# V-00780-00.net
KiCad netlist of a schematic drawn in EAGLE
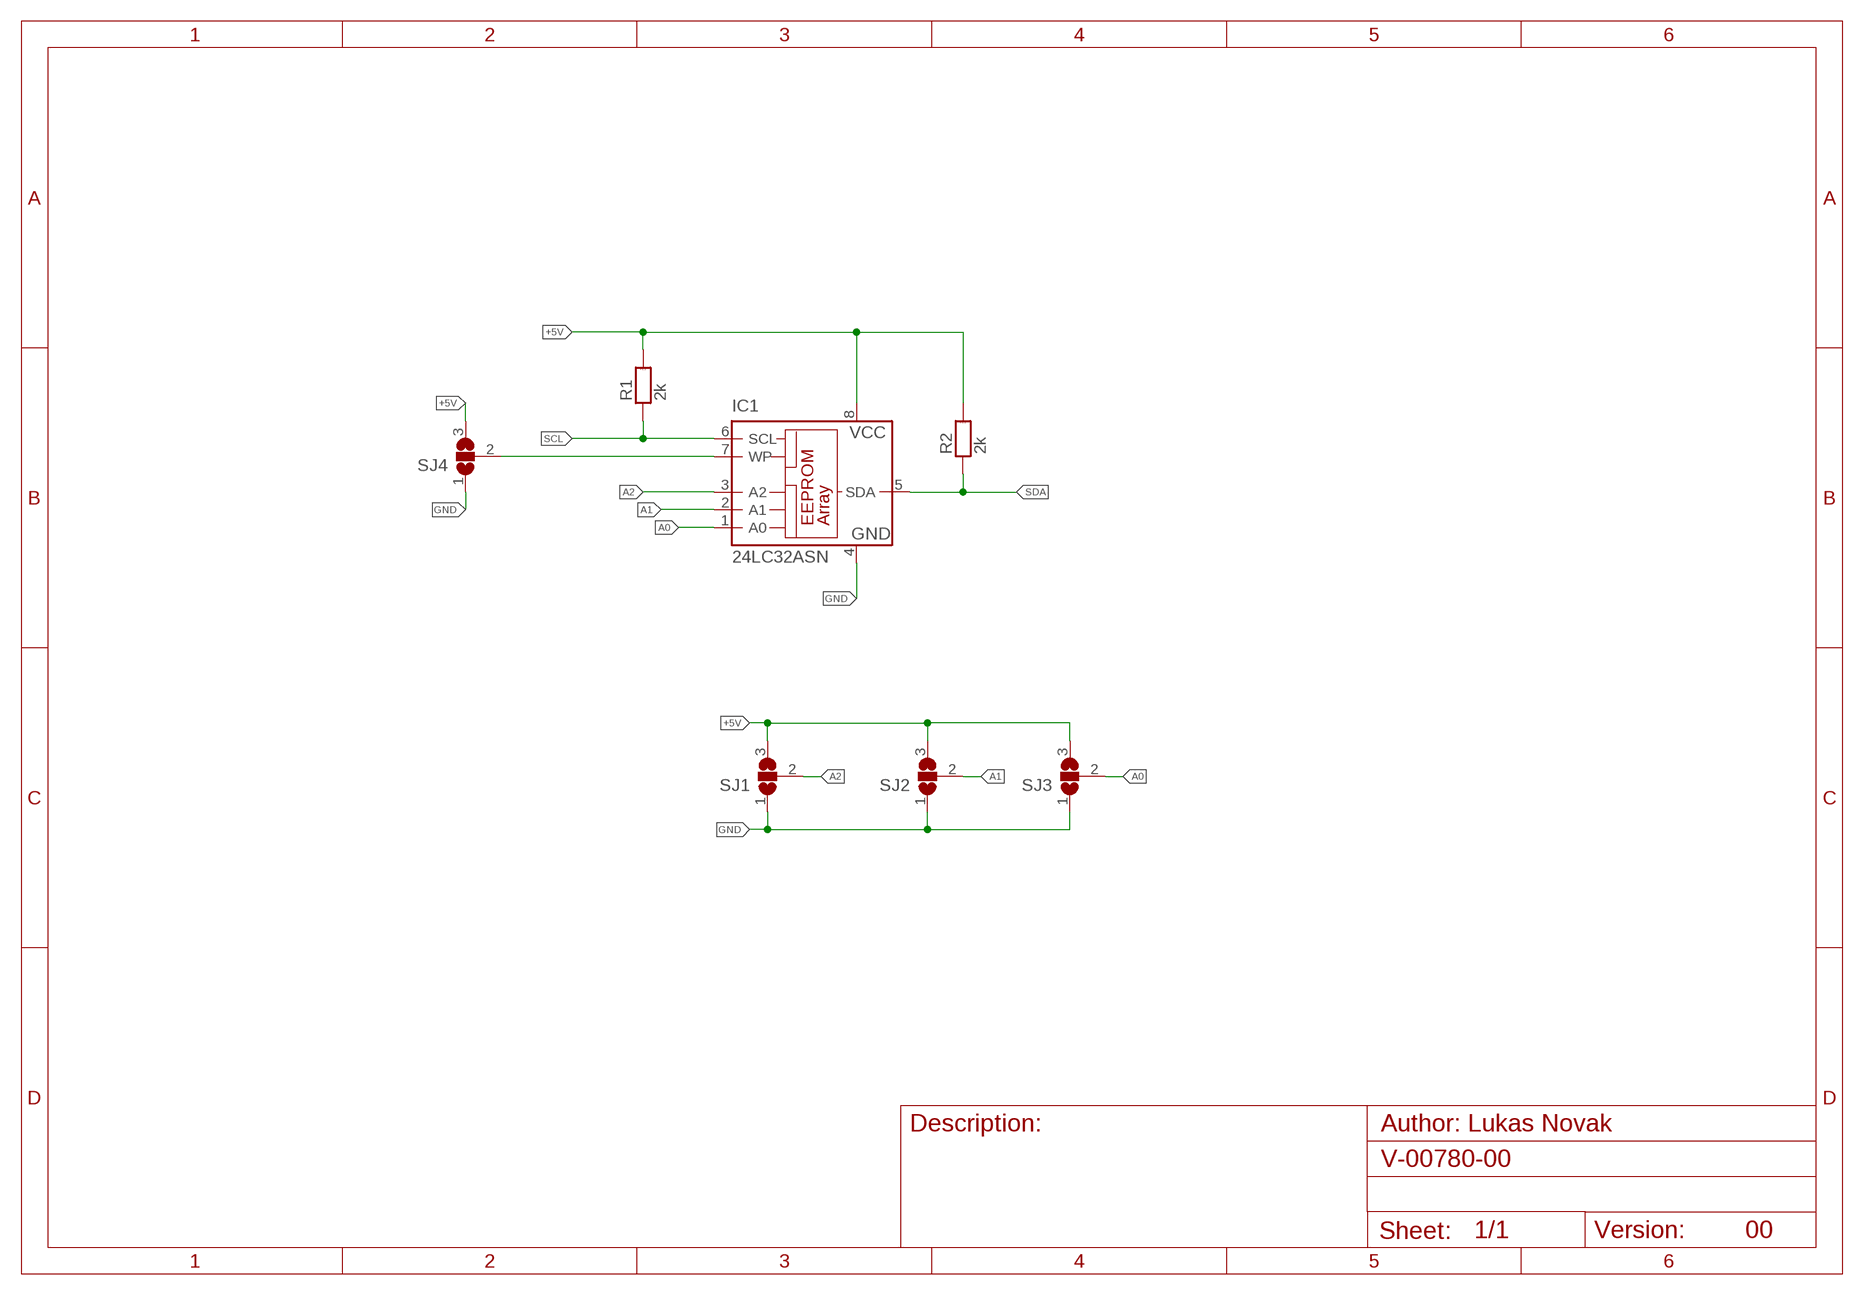
[diagram p0: schematic, sheet 1]

(export (version "E")
  (design (tool "Eeschema 10.0.6"))
  (components
    (comp (ref "IC1")
      (value "24LC32ASN")
      (footprint "eagle-import:SO-08")
      (fields (field (name "MF") "MICROCHIP") (field (name "MPN") "24LC32A/SN"))
      (libsource (lib "eagle-import") (part "24SNLC32A"))
    )
    (comp (ref "R1")
      (value "2k")
      (footprint "eagle-import:1206")
      (libsource (lib "eagle-import") (part "R_1206"))
    )
    (comp (ref "R2")
      (value "2k")
      (footprint "eagle-import:1206")
      (libsource (lib "eagle-import") (part "R_1206"))
    )
    (comp (ref "SJ1")
      (value "SJ2W")
      (footprint "eagle-import:SJ_2")
      (libsource (lib "eagle-import") (part "SJ2W"))
    )
    (comp (ref "SJ2")
      (value "SJ2W")
      (footprint "eagle-import:SJ_2")
      (libsource (lib "eagle-import") (part "SJ2W"))
    )
    (comp (ref "SJ3")
      (value "SJ2W")
      (footprint "eagle-import:SJ_2")
      (libsource (lib "eagle-import") (part "SJ2W"))
    )
    (comp (ref "SJ4")
      (value "SJ2W")
      (footprint "eagle-import:SJ_2")
      (libsource (lib "eagle-import") (part "SJ2W"))
    )
  )
  (nets
    (net (code "1") (name "+5V") (class "Default")
      (node (ref "IC1") (pin "8") (pinfunction "VCC_8") (pintype "power_in"))
      (node (ref "R1") (pin "2") (pinfunction "2_2") (pintype "passive"))
      (node (ref "R2") (pin "2") (pinfunction "2_2") (pintype "passive"))
      (node (ref "SJ1") (pin "3") (pinfunction "3_3") (pintype "passive"))
      (node (ref "SJ2") (pin "3") (pinfunction "3_3") (pintype "passive"))
      (node (ref "SJ3") (pin "3") (pinfunction "3_3") (pintype "passive"))
      (node (ref "SJ4") (pin "3") (pinfunction "3_3") (pintype "passive"))
    )
    (net (code "2") (name "A0") (class "Default")
      (node (ref "IC1") (pin "1") (pinfunction "A0_1") (pintype "input"))
      (node (ref "SJ3") (pin "2") (pinfunction "2_2") (pintype "passive"))
    )
    (net (code "3") (name "A1") (class "Default")
      (node (ref "IC1") (pin "2") (pinfunction "A1_2") (pintype "input"))
      (node (ref "SJ2") (pin "2") (pinfunction "2_2") (pintype "passive"))
    )
    (net (code "4") (name "A2") (class "Default")
      (node (ref "IC1") (pin "3") (pinfunction "A2_3") (pintype "input"))
      (node (ref "SJ1") (pin "2") (pinfunction "2_2") (pintype "passive"))
    )
    (net (code "5") (name "GND") (class "Default")
      (node (ref "IC1") (pin "4") (pinfunction "GND_4") (pintype "power_in"))
      (node (ref "SJ1") (pin "1") (pinfunction "1_1") (pintype "passive"))
      (node (ref "SJ2") (pin "1") (pinfunction "1_1") (pintype "passive"))
      (node (ref "SJ3") (pin "1") (pinfunction "1_1") (pintype "passive"))
      (node (ref "SJ4") (pin "1") (pinfunction "1_1") (pintype "passive"))
    )
    (net (code "6") (name "Net-(IC1-WP)") (class "Default")
      (node (ref "IC1") (pin "7") (pinfunction "WP_7") (pintype "input"))
      (node (ref "SJ4") (pin "2") (pinfunction "2_2") (pintype "passive"))
    )
    (net (code "7") (name "SCL") (class "Default")
      (node (ref "IC1") (pin "6") (pinfunction "SCL_6") (pintype "input"))
      (node (ref "R1") (pin "1") (pinfunction "1_1") (pintype "passive"))
    )
    (net (code "8") (name "SDA") (class "Default")
      (node (ref "IC1") (pin "5") (pinfunction "SDA_5") (pintype "bidirectional"))
      (node (ref "R2") (pin "1") (pinfunction "1_1") (pintype "passive"))
    )
  )
)
